# Adafruit_PowerBoost_500_Basic.net
KiCad netlist of a schematic drawn in EAGLE
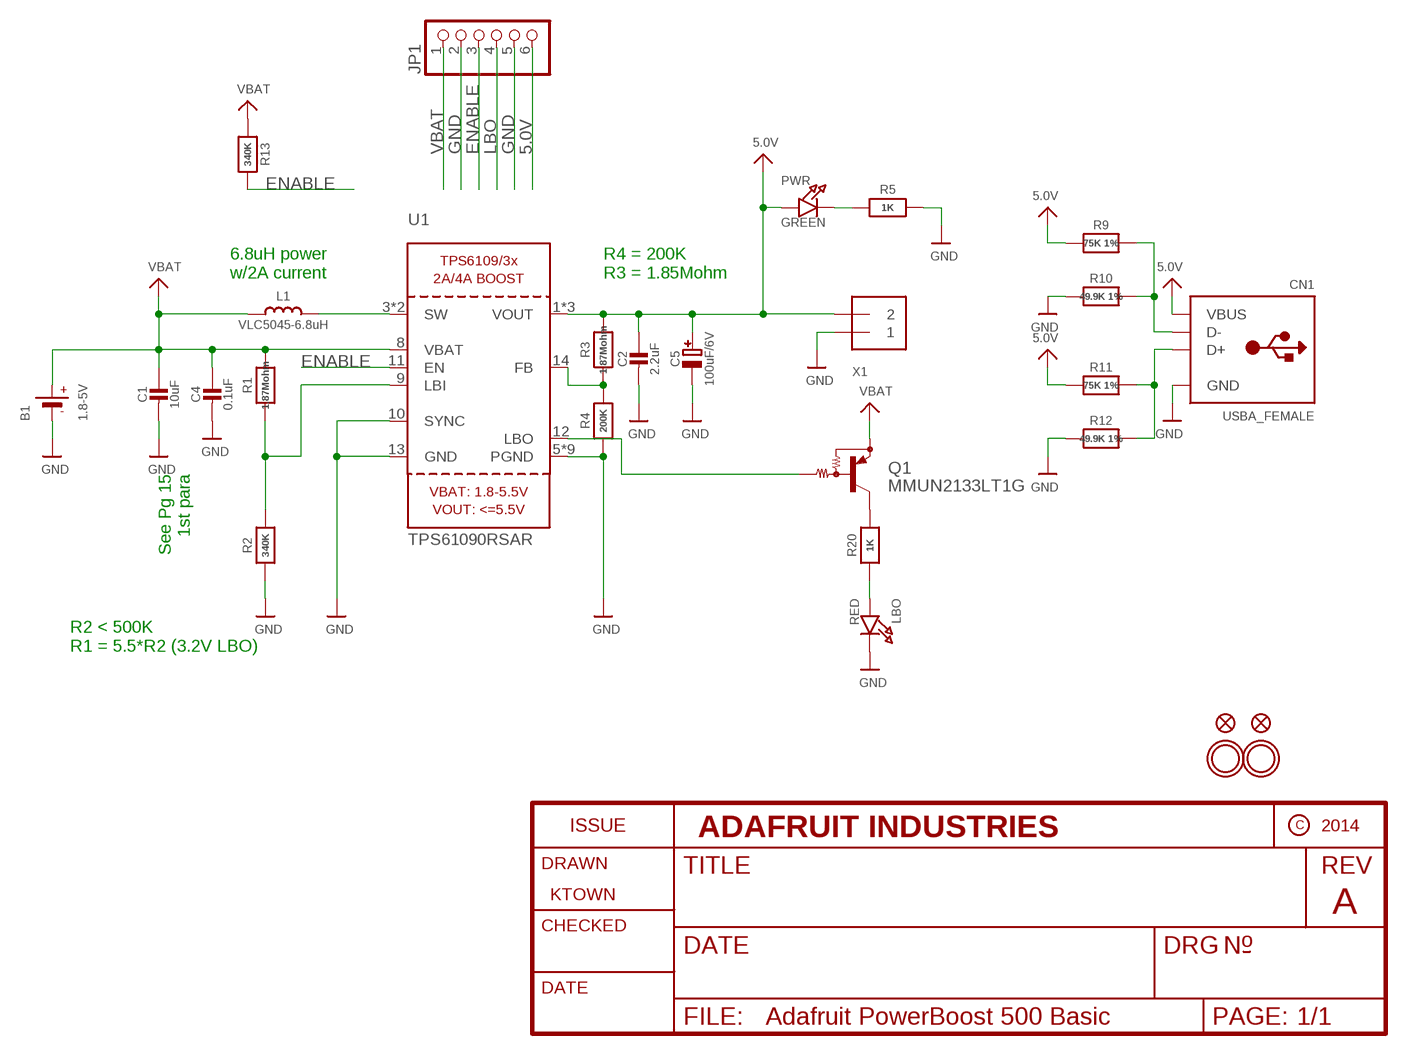
[diagram p0: schematic, sheet 1]

(export (version "E")
  (design (tool "Eeschema 10.0.6"))
  (components
    (comp (ref "B1")
      (value "1.8-5V")
      (footprint "eagle-import:JSTPH2")
      (libsource (lib "eagle-import") (part "BATTERY"))
    )
    (comp (ref "C1")
      (value "10uF")
      (footprint "eagle-import:0805-NO")
      (libsource (lib "eagle-import") (part "CAP_CERAMIC0805-NOOUTLINE"))
    )
    (comp (ref "C2")
      (value "2.2uF")
      (footprint "eagle-import:0805-NO")
      (libsource (lib "eagle-import") (part "CAP_CERAMIC0805-NOOUTLINE"))
    )
    (comp (ref "C4")
      (value "0.1uF")
      (footprint "eagle-import:0805-NO")
      (libsource (lib "eagle-import") (part "CAP_CERAMIC0805-NOOUTLINE"))
    )
    (comp (ref "C5")
      (value "100uF/6V")
      (footprint "eagle-import:EIA3528-21_B-R")
      (libsource (lib "eagle-import") (part "CAP_TANTALUMB/3528_REFLOW"))
    )
    (comp (ref "CN1")
      (value "USBA_FEMALE")
      (footprint "eagle-import:USB_HOST-PTH")
      (libsource (lib "eagle-import") (part "USB_TYPEAPTHFML"))
    )
    (comp (ref "FID2")
      (value "FIDUCIAL\"\"")
      (footprint "eagle-import:FIDUCIAL_1MM")
      (libsource (lib "eagle-import") (part "FIDUCIAL{dblquote}{dblquote}"))
    )
    (comp (ref "FID3")
      (value "FIDUCIAL\"\"")
      (footprint "eagle-import:FIDUCIAL_1MM")
      (fields (field (name "BOM") "EXCLUDE"))
      (libsource (lib "eagle-import") (part "FIDUCIAL{dblquote}{dblquote}"))
    )
    (comp (ref "JP1")
      (value "PINHD-1X6CB")
      (footprint "eagle-import:1X06-CLEANBIG")
      (libsource (lib "eagle-import") (part "PINHD-1X6CB"))
    )
    (comp (ref "L1")
      (value "VLC5045-6.8uH")
      (footprint "eagle-import:INDUCTOR_5X5MM_TDK_VLC5045")
      (libsource (lib "eagle-import") (part "INDUCTORTDK_VLC5045"))
    )
    (comp (ref "LBO")
      (value "RED")
      (footprint "eagle-import:CHIPLED_0805_NOOUTLINE")
      (libsource (lib "eagle-import") (part "LED0805_NOOUTLINE"))
    )
    (comp (ref "PWR")
      (value "GREEN")
      (footprint "eagle-import:CHIPLED_0805_NOOUTLINE")
      (libsource (lib "eagle-import") (part "LED0805_NOOUTLINE"))
    )
    (comp (ref "Q1")
      (value "MMUN2133LT1G")
      (footprint "eagle-import:SC59-BEC")
      (libsource (lib "eagle-import") (part "-PNP_DRIVER-SC59-BECMUN2114T1"))
    )
    (comp (ref "R1")
      (value "1.87Mohm")
      (footprint "eagle-import:0805-NO")
      (libsource (lib "eagle-import") (part "RESISTOR0805_NOOUTLINE"))
    )
    (comp (ref "R2")
      (value "340K")
      (footprint "eagle-import:0805-NO")
      (libsource (lib "eagle-import") (part "RESISTOR0805_NOOUTLINE"))
    )
    (comp (ref "R3")
      (value "1.87Mohm")
      (footprint "eagle-import:0805-NO")
      (libsource (lib "eagle-import") (part "RESISTOR0805_NOOUTLINE"))
    )
    (comp (ref "R4")
      (value "200K")
      (footprint "eagle-import:0805-NO")
      (libsource (lib "eagle-import") (part "RESISTOR0805_NOOUTLINE"))
    )
    (comp (ref "R5")
      (value "1K")
      (footprint "eagle-import:0805-NO")
      (libsource (lib "eagle-import") (part "RESISTOR0805_NOOUTLINE"))
    )
    (comp (ref "R9")
      (value "75K 1%")
      (footprint "eagle-import:0805-NO")
      (libsource (lib "eagle-import") (part "RESISTOR0805_NOOUTLINE"))
    )
    (comp (ref "R10")
      (value "49.9K 1%")
      (footprint "eagle-import:0805-NO")
      (libsource (lib "eagle-import") (part "RESISTOR0805_NOOUTLINE"))
    )
    (comp (ref "R11")
      (value "75K 1%")
      (footprint "eagle-import:0805-NO")
      (libsource (lib "eagle-import") (part "RESISTOR0805_NOOUTLINE"))
    )
    (comp (ref "R12")
      (value "49.9K 1%")
      (footprint "eagle-import:0805-NO")
      (libsource (lib "eagle-import") (part "RESISTOR0805_NOOUTLINE"))
    )
    (comp (ref "R13")
      (value "340K")
      (footprint "eagle-import:0805-NO")
      (libsource (lib "eagle-import") (part "RESISTOR0805_NOOUTLINE"))
    )
    (comp (ref "R20")
      (value "1K")
      (footprint "eagle-import:0805-NO")
      (libsource (lib "eagle-import") (part "RESISTOR0805_NOOUTLINE"))
    )
    (comp (ref "U$10")
      (value "MOUNTINGHOLE2.5")
      (footprint "eagle-import:MOUNTINGHOLE_2.5_PLATED")
      (libsource (lib "eagle-import") (part "MOUNTINGHOLE2.5"))
    )
    (comp (ref "U$12")
      (value "MOUNTINGHOLE2.5")
      (footprint "eagle-import:MOUNTINGHOLE_2.5_PLATED")
      (libsource (lib "eagle-import") (part "MOUNTINGHOLE2.5"))
    )
    (comp (ref "U1")
      (value "TPS61090RSAR")
      (footprint "eagle-import:PVQFN-16")
      (libsource (lib "eagle-import") (part "VREG_TPS6103X"))
    )
    (comp (ref "X1")
      (value "TERMBLOCK_1X2")
      (footprint "eagle-import:TERMBLOCK_1X2-3.5MM")
      (libsource (lib "eagle-import") (part "TERMBLOCK_1X2"))
    )
  )
  (nets
    (net (code "1") (name "/ENABLE") (class "Default")
      (node (ref "JP1") (pin "3") (pinfunction "3_3") (pintype "passive"))
      (node (ref "R13") (pin "2") (pinfunction "2_2") (pintype "passive"))
      (node (ref "U1") (pin "11") (pinfunction "EN_11") (pintype "input"))
    )
    (net (code "2") (name "/LBO") (class "Default")
      (node (ref "JP1") (pin "4") (pinfunction "4_4") (pintype "passive"))
      (node (ref "Q1") (pin "B") (pinfunction "B_B") (pintype "passive"))
      (node (ref "U1") (pin "12") (pinfunction "LBO_12") (pintype "output"))
    )
    (net (code "3") (name "5.0V") (class "Default")
      (node (ref "C2") (pin "1") (pinfunction "1_1") (pintype "passive"))
      (node (ref "C5") (pin "+") (pinfunction "+_+") (pintype "passive"))
      (node (ref "CN1") (pin "VBUS") (pinfunction "VBUS_VBUS") (pintype "power_in"))
      (node (ref "JP1") (pin "6") (pinfunction "6_6") (pintype "passive"))
      (node (ref "PWR") (pin "A") (pinfunction "A_A") (pintype "passive"))
      (node (ref "R11") (pin "2") (pinfunction "2_2") (pintype "passive"))
      (node (ref "R3") (pin "2") (pinfunction "2_2") (pintype "passive"))
      (node (ref "R9") (pin "2") (pinfunction "2_2") (pintype "passive"))
      (node (ref "U1") (pin "1") (pinfunction "VOUT_1") (pintype "power_in"))
      (node (ref "U1") (pin "15") (pinfunction "VOUT_15") (pintype "power_in"))
      (node (ref "U1") (pin "16") (pinfunction "VOUT_16") (pintype "power_in"))
      (node (ref "X1") (pin "2") (pinfunction "2_2") (pintype "passive"))
    )
    (net (code "4") (name "GND") (class "Default")
      (node (ref "B1") (pin "1") (pinfunction "-_1") (pintype "passive"))
      (node (ref "C1") (pin "2") (pinfunction "2_2") (pintype "passive"))
      (node (ref "C2") (pin "2") (pinfunction "2_2") (pintype "passive"))
      (node (ref "C4") (pin "2") (pinfunction "2_2") (pintype "passive"))
      (node (ref "C5") (pin "-") (pinfunction "-_-") (pintype "passive"))
      (node (ref "CN1") (pin "GND") (pinfunction "GND_GND") (pintype "power_in"))
      (node (ref "JP1") (pin "2") (pinfunction "2_2") (pintype "passive"))
      (node (ref "JP1") (pin "5") (pinfunction "5_5") (pintype "passive"))
      (node (ref "LBO") (pin "C") (pinfunction "C_C") (pintype "passive"))
      (node (ref "R10") (pin "2") (pinfunction "2_2") (pintype "passive"))
      (node (ref "R12") (pin "2") (pinfunction "2_2") (pintype "passive"))
      (node (ref "R2") (pin "1") (pinfunction "1_1") (pintype "passive"))
      (node (ref "R4") (pin "1") (pinfunction "1_1") (pintype "passive"))
      (node (ref "R5") (pin "2") (pinfunction "2_2") (pintype "passive"))
      (node (ref "U1") (pin "10") (pinfunction "SYNC_10") (pintype "input"))
      (node (ref "U1") (pin "13") (pinfunction "GND_13") (pintype "power_in"))
      (node (ref "U1") (pin "5") (pinfunction "PGND_5") (pintype "power_in"))
      (node (ref "U1") (pin "6") (pinfunction "PGND_6") (pintype "power_in"))
      (node (ref "U1") (pin "7") (pinfunction "PGND_7") (pintype "power_in"))
      (node (ref "U1") (pin "P$18") (pinfunction "PGND_P$18") (pintype "power_in"))
      (node (ref "U1") (pin "P$19") (pinfunction "PGND_P$19") (pintype "power_in"))
      (node (ref "U1") (pin "P$20") (pinfunction "PGND_P$20") (pintype "power_in"))
      (node (ref "U1") (pin "P$21") (pinfunction "PGND_P$21") (pintype "power_in"))
      (node (ref "U1") (pin "P$22") (pinfunction "PGND_P$22") (pintype "power_in"))
      (node (ref "U1") (pin "THERMAL") (pinfunction "PGND_THERMAL") (pintype "power_in"))
      (node (ref "X1") (pin "1") (pinfunction "1_1") (pintype "passive"))
    )
    (net (code "5") (name "Net-(CN1-PadD+)") (class "Default")
      (node (ref "CN1") (pin "D+") (pinfunction "D+_D+") (pintype "bidirectional"))
      (node (ref "R11") (pin "1") (pinfunction "1_1") (pintype "passive"))
      (node (ref "R12") (pin "1") (pinfunction "1_1") (pintype "passive"))
    )
    (net (code "6") (name "Net-(CN1-PadD-)") (class "Default")
      (node (ref "CN1") (pin "D-") (pinfunction "D-_D-") (pintype "bidirectional"))
      (node (ref "R10") (pin "1") (pinfunction "1_1") (pintype "passive"))
      (node (ref "R9") (pin "1") (pinfunction "1_1") (pintype "passive"))
    )
    (net (code "7") (name "Net-(L1-2)") (class "Default")
      (node (ref "L1") (pin "P$2") (pinfunction "2_P$2") (pintype "passive"))
      (node (ref "U1") (pin "3") (pinfunction "SW_3") (pintype "input"))
      (node (ref "U1") (pin "4") (pinfunction "SW_4") (pintype "input"))
    )
    (net (code "8") (name "Net-(LBO-PadA)") (class "Default")
      (node (ref "LBO") (pin "A") (pinfunction "A_A") (pintype "passive"))
      (node (ref "R20") (pin "1") (pinfunction "1_1") (pintype "passive"))
    )
    (net (code "9") (name "Net-(PWR-PadC)") (class "Default")
      (node (ref "PWR") (pin "C") (pinfunction "C_C") (pintype "passive"))
      (node (ref "R5") (pin "1") (pinfunction "1_1") (pintype "passive"))
    )
    (net (code "10") (name "Net-(Q1-PadC)") (class "Default")
      (node (ref "Q1") (pin "C") (pinfunction "C_C") (pintype "passive"))
      (node (ref "R20") (pin "2") (pinfunction "2_2") (pintype "passive"))
    )
    (net (code "11") (name "Net-(U1-FB)") (class "Default")
      (node (ref "R3") (pin "1") (pinfunction "1_1") (pintype "passive"))
      (node (ref "R4") (pin "2") (pinfunction "2_2") (pintype "passive"))
      (node (ref "U1") (pin "14") (pinfunction "FB_14") (pintype "input"))
    )
    (net (code "12") (name "Net-(U1-LBI)") (class "Default")
      (node (ref "R1") (pin "1") (pinfunction "1_1") (pintype "passive"))
      (node (ref "R2") (pin "2") (pinfunction "2_2") (pintype "passive"))
      (node (ref "U1") (pin "9") (pinfunction "LBI_9") (pintype "input"))
    )
    (net (code "13") (name "VBAT") (class "Default")
      (node (ref "B1") (pin "2") (pinfunction "+_2") (pintype "passive"))
      (node (ref "C1") (pin "1") (pinfunction "1_1") (pintype "passive"))
      (node (ref "C4") (pin "1") (pinfunction "1_1") (pintype "passive"))
      (node (ref "JP1") (pin "1") (pinfunction "1_1") (pintype "passive"))
      (node (ref "L1") (pin "P$1") (pinfunction "1_P$1") (pintype "passive"))
      (node (ref "Q1") (pin "E") (pinfunction "E_E") (pintype "passive"))
      (node (ref "R1") (pin "2") (pinfunction "2_2") (pintype "passive"))
      (node (ref "R13") (pin "1") (pinfunction "1_1") (pintype "passive"))
      (node (ref "U1") (pin "8") (pinfunction "VBAT_8") (pintype "input"))
    )
  )
)
